# DoorC.net
KiCad netlist of a schematic drawn in EAGLE
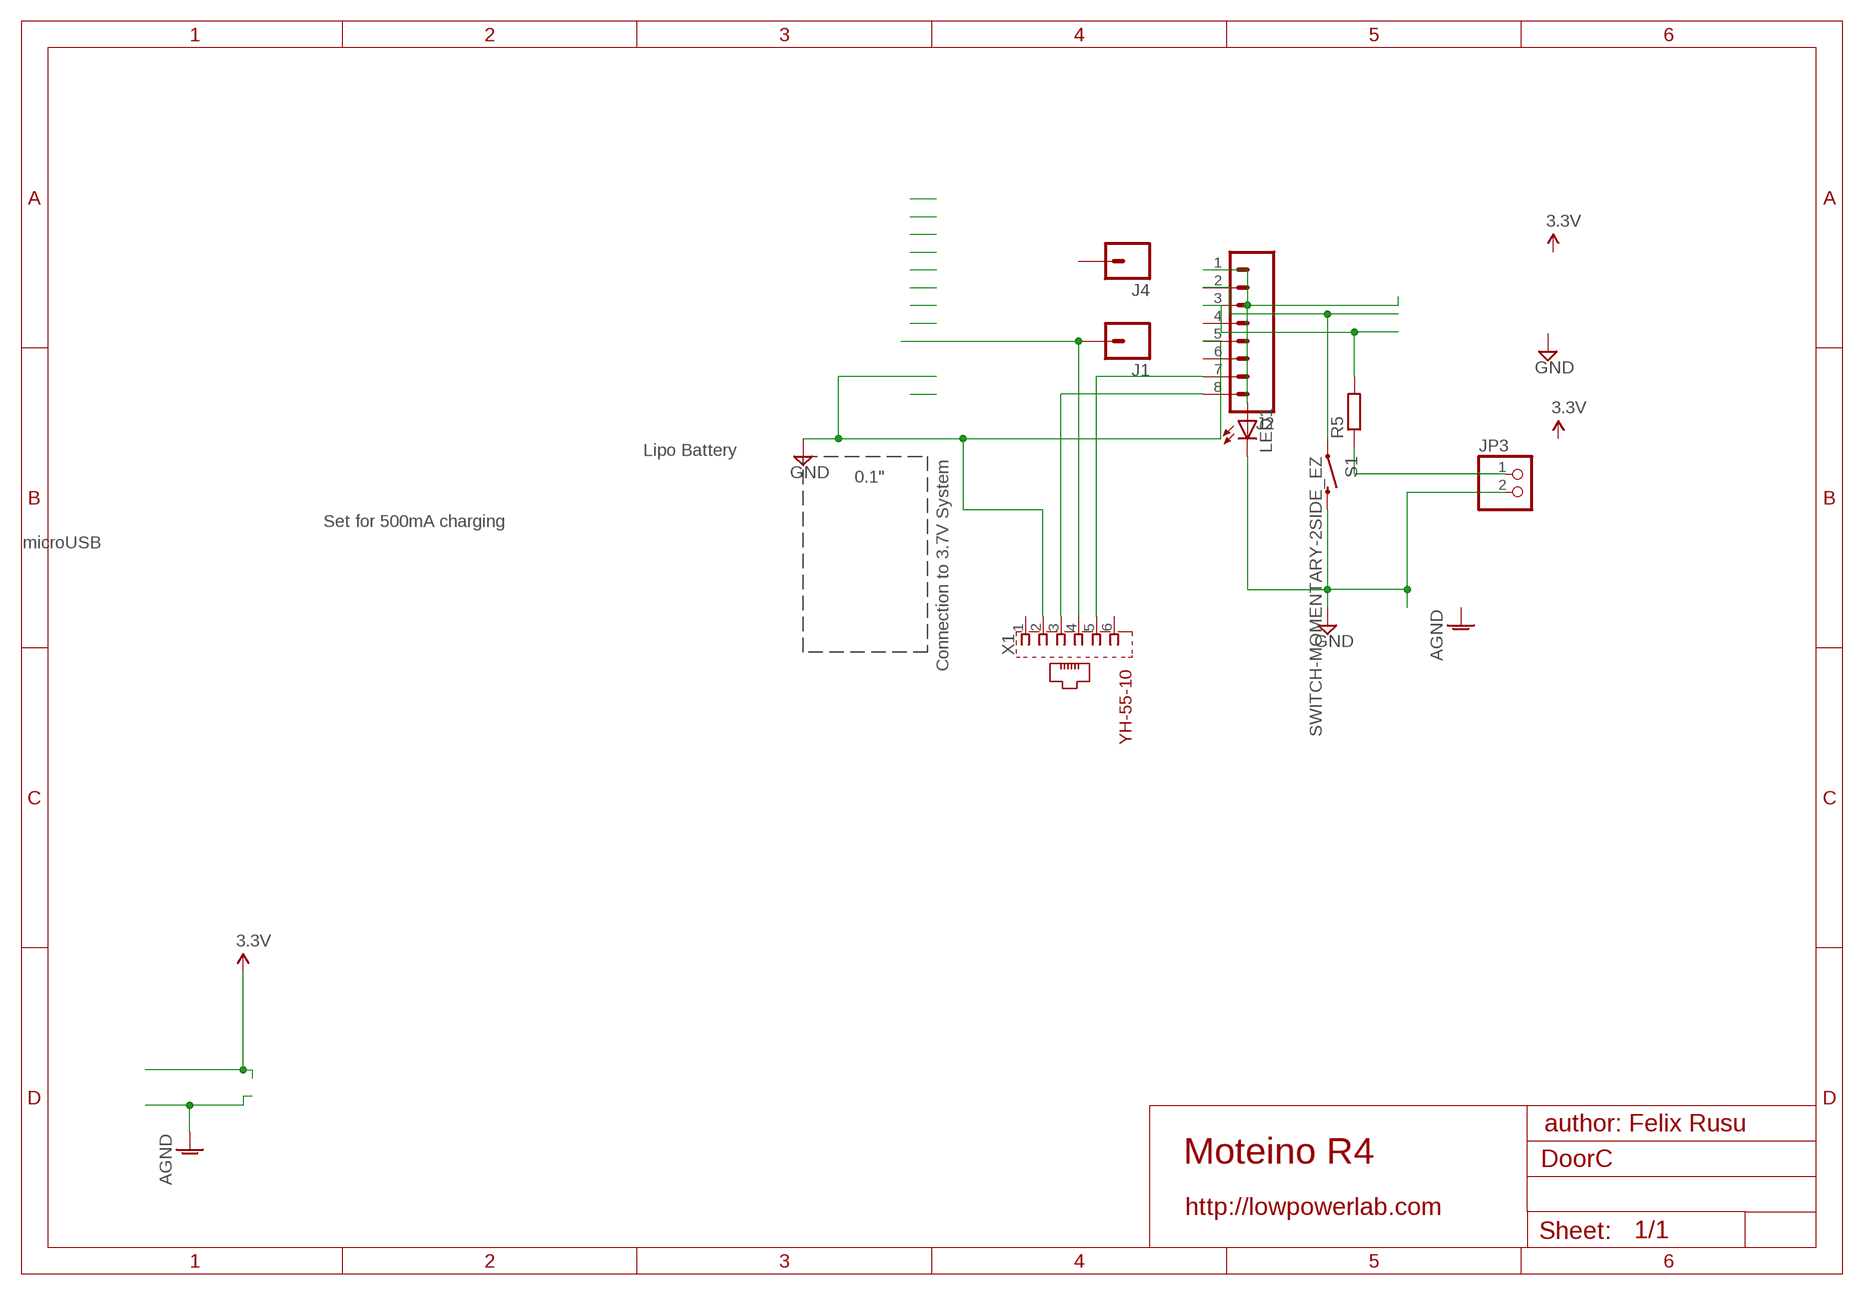
[diagram p0: schematic, sheet 1]

(export (version "E")
  (design (tool "Eeschema 10.0.6"))
  (components
    (comp (ref "J1")
      (value "M01PTH")
      (footprint "eagle-import:1X01")
      (libsource (lib "eagle-import") (part "M01PTH"))
    )
    (comp (ref "J2")
      (value "M08SILK_FEMALE_PTH")
      (footprint "eagle-import:1X08")
      (libsource (lib "eagle-import") (part "M08SILK_FEMALE_PTH"))
    )
    (comp (ref "J4")
      (value "M01PTH")
      (footprint "eagle-import:1X01")
      (libsource (lib "eagle-import") (part "M01PTH"))
    )
    (comp (ref "JP3")
      (value "PINHD-1X2")
      (footprint "eagle-import:1X02")
      (libsource (lib "eagle-import") (part "PINHD-1X2"))
    )
    (comp (ref "LED1")
      (value "LED3MM")
      (footprint "eagle-import:LED3MM")
      (libsource (lib "eagle-import") (part "LED3MM"))
    )
    (comp (ref "R5")
      (value "R-EU_0204/7")
      (footprint "eagle-import:0204_7")
      (libsource (lib "eagle-import") (part "R-EU_0204/7"))
    )
    (comp (ref "S1")
      (value "SWITCH-MOMENTARY-2SIDE_EZ")
      (footprint "eagle-import:TACTILE-PTH-SIDEEZ")
      (libsource (lib "eagle-import") (part "SWITCH-MOMENTARY-2SIDE_EZ"))
    )
    (comp (ref "X1")
      (value "YH-55-10")
      (footprint "eagle-import:YH-55-10")
      (libsource (lib "eagle-import") (part "YH-55-10"))
    )
  )
  (nets
    (net (code "3") (name "GND") (class "Default")
      (node (ref "J2") (pin "5") (pinfunction "5_5") (pintype "passive"))
      (node (ref "JP3") (pin "2") (pinfunction "2_2") (pintype "passive"))
      (node (ref "LED1") (pin "K") (pinfunction "C_K") (pintype "passive"))
      (node (ref "S1") (pin "2") (pinfunction "2_2") (pintype "passive"))
      (node (ref "X1") (pin "2") (pinfunction "2_2") (pintype "passive"))
    )
    (net (code "4") (name "Net-(J1-Pad1)") (class "Default")
      (node (ref "J1") (pin "1") (pinfunction "1_1") (pintype "passive"))
      (node (ref "X1") (pin "4") (pinfunction "4_4") (pintype "passive"))
    )
    (net (code "5") (name "Net-(J2-Pad1)") (class "Default")
      (node (ref "J2") (pin "1") (pinfunction "1_1") (pintype "passive"))
      (node (ref "LED1") (pin "A") (pinfunction "A_A") (pintype "passive"))
    )
    (net (code "6") (name "Net-(J2-Pad2)") (class "Default")
      (node (ref "J2") (pin "2") (pinfunction "2_2") (pintype "passive"))
      (node (ref "S1") (pin "1") (pinfunction "1_1") (pintype "passive"))
    )
    (net (code "7") (name "Net-(J2-Pad3)") (class "Default")
      (node (ref "J2") (pin "3") (pinfunction "3_3") (pintype "passive"))
      (node (ref "R5") (pin "2") (pinfunction "2_2") (pintype "passive"))
    )
    (net (code "8") (name "Net-(J2-Pad7)") (class "Default")
      (node (ref "J2") (pin "7") (pinfunction "7_7") (pintype "passive"))
      (node (ref "X1") (pin "5") (pinfunction "5_5") (pintype "passive"))
    )
    (net (code "9") (name "Net-(J2-Pad8)") (class "Default")
      (node (ref "J2") (pin "8") (pinfunction "8_8") (pintype "passive"))
      (node (ref "X1") (pin "3") (pinfunction "3_3") (pintype "passive"))
    )
    (net (code "10") (name "Net-(JP3-Pad1)") (class "Default")
      (node (ref "JP3") (pin "1") (pinfunction "1_1") (pintype "passive"))
      (node (ref "R5") (pin "1") (pinfunction "1_1") (pintype "passive"))
    )
    (net (code "11") (name "unconnected-(J2-Pad4)") (class "Default")
      (node (ref "J2") (pin "4") (pinfunction "4_4") (pintype "passive"))
    )
    (net (code "12") (name "unconnected-(J2-Pad6)") (class "Default")
      (node (ref "J2") (pin "6") (pinfunction "6_6") (pintype "passive"))
    )
    (net (code "13") (name "unconnected-(J4-Pad1)") (class "Default")
      (node (ref "J4") (pin "1") (pinfunction "1_1") (pintype "passive"))
    )
    (net (code "14") (name "unconnected-(X1-Pad1)") (class "Default")
      (node (ref "X1") (pin "1") (pinfunction "1_1") (pintype "passive"))
    )
    (net (code "15") (name "unconnected-(X1-Pad6)") (class "Default")
      (node (ref "X1") (pin "6") (pinfunction "6_6") (pintype "passive"))
    )
  )
)
